# md2pce.net
KiCad netlist of a schematic drawn in EAGLE
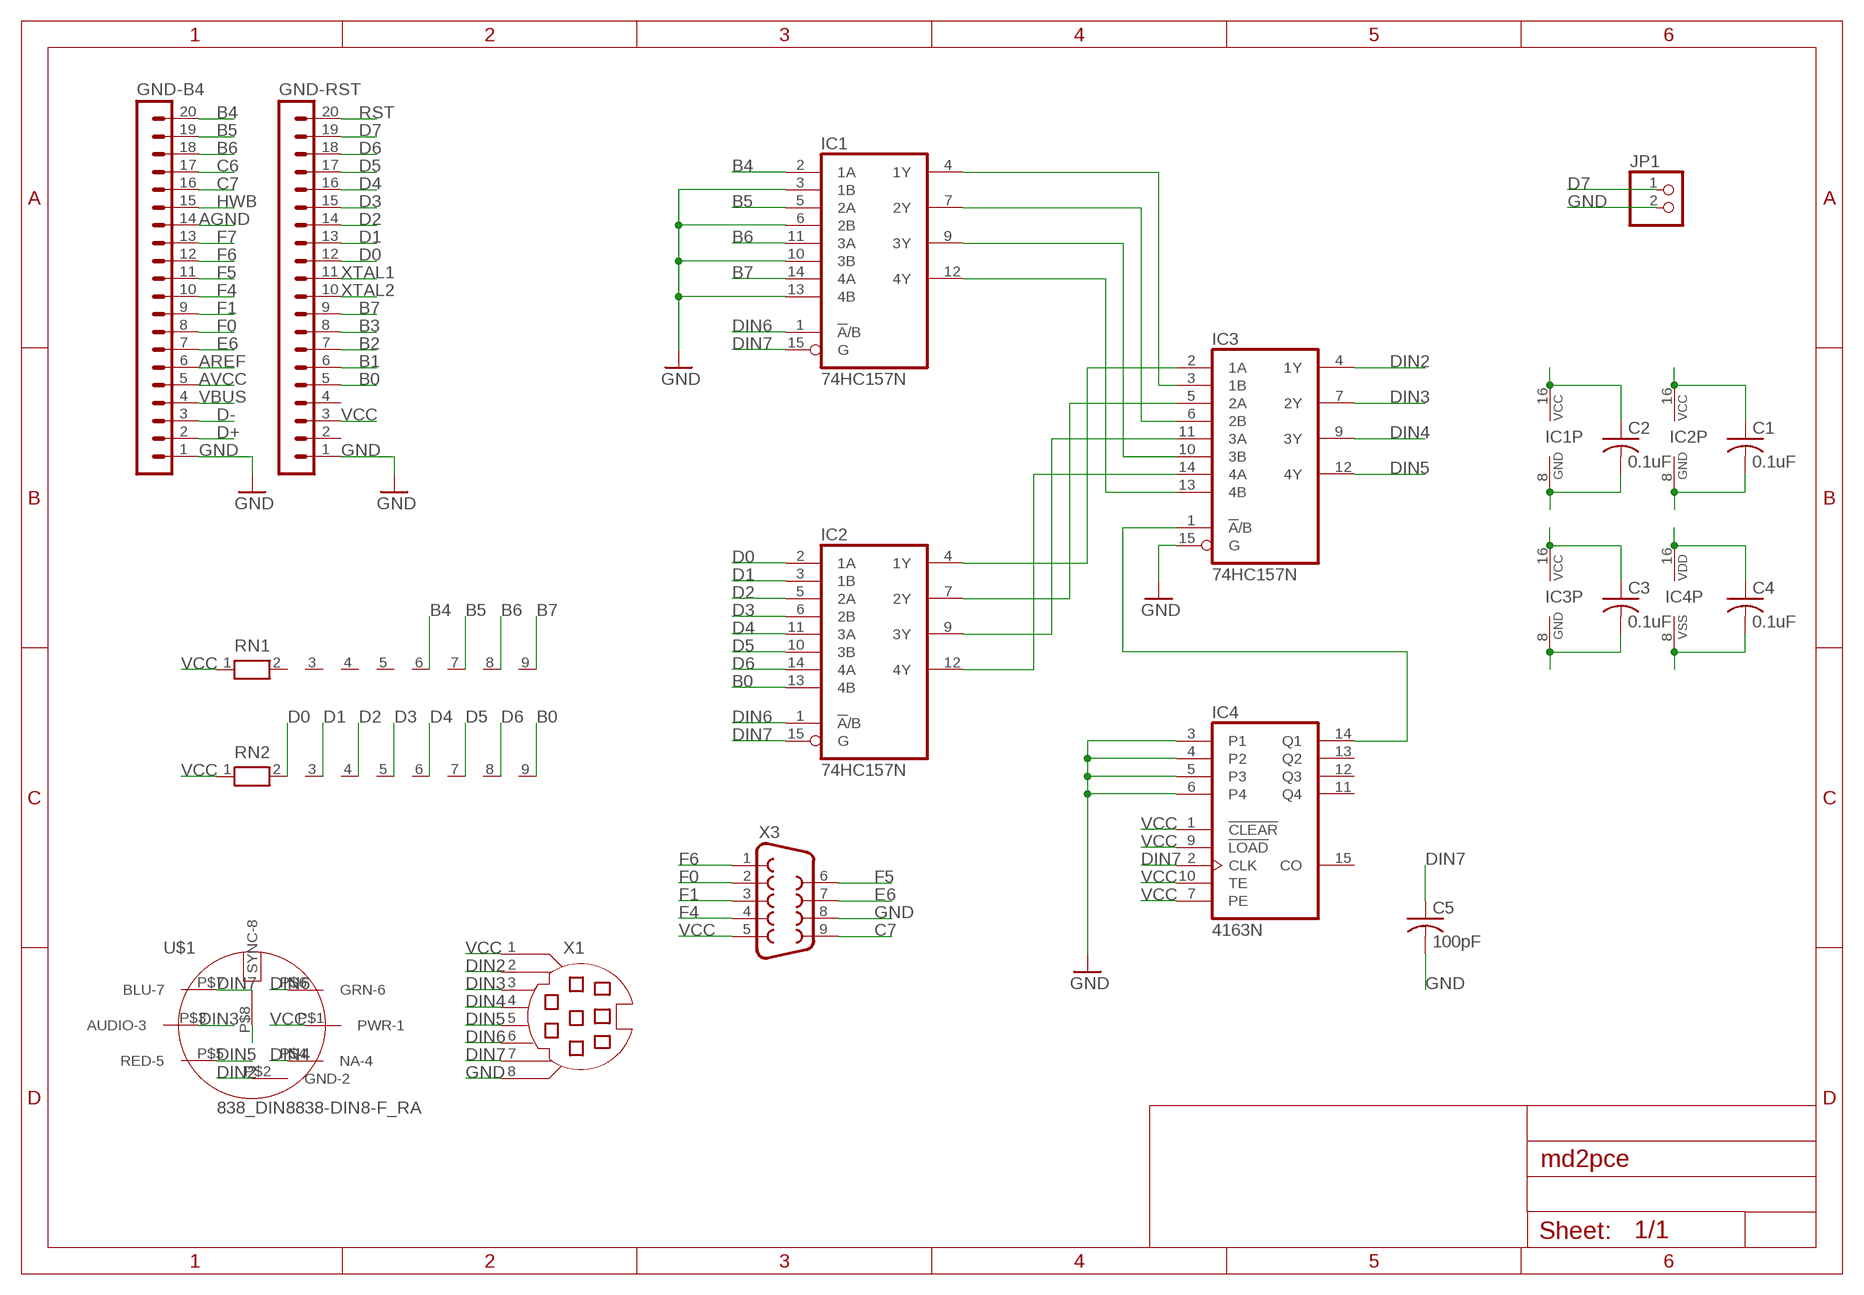
[diagram p0: schematic, sheet 1]

(export (version "E")
  (design (tool "Eeschema 10.0.6"))
  (components
    (comp (ref "C1")
      (value "0.1uF")
      (footprint "eagle-import:C025-024X044")
      (libsource (lib "eagle-import") (part "C-US025-024X044"))
    )
    (comp (ref "C2")
      (value "0.1uF")
      (footprint "eagle-import:C025-024X044")
      (libsource (lib "eagle-import") (part "C-US025-024X044"))
    )
    (comp (ref "C3")
      (value "0.1uF")
      (footprint "eagle-import:C025-024X044")
      (libsource (lib "eagle-import") (part "C-US025-024X044"))
    )
    (comp (ref "C4")
      (value "0.1uF")
      (footprint "eagle-import:C025-024X044")
      (libsource (lib "eagle-import") (part "C-US025-024X044"))
    )
    (comp (ref "C5")
      (value "100pF")
      (footprint "eagle-import:C025-024X044")
      (libsource (lib "eagle-import") (part "C-US025-024X044"))
    )
    (comp (ref "GND-B4")
      (value "MA20-1")
      (footprint "eagle-import:MA20-1")
      (libsource (lib "eagle-import") (part "MA20-1"))
    )
    (comp (ref "GND-RST")
      (value "MA20-1")
      (footprint "eagle-import:MA20-1")
      (libsource (lib "eagle-import") (part "MA20-1"))
    )
    (comp (ref "IC1")
      (value "74HC157N")
      (footprint "eagle-import:DIL16")
      (libsource (lib "eagle-import") (part "74157NHC"))
    )
    (comp (ref "IC2")
      (value "74HC157N")
      (footprint "eagle-import:DIL16")
      (libsource (lib "eagle-import") (part "74157NHC"))
    )
    (comp (ref "IC3")
      (value "74HC157N")
      (footprint "eagle-import:DIL16")
      (libsource (lib "eagle-import") (part "74157NHC"))
    )
    (comp (ref "IC4")
      (value "4163N")
      (footprint "eagle-import:DIL16")
      (libsource (lib "eagle-import") (part "4163N"))
    )
    (comp (ref "JP1")
      (value "PINHD-1X2")
      (footprint "eagle-import:1X02")
      (libsource (lib "eagle-import") (part "PINHD-1X2"))
    )
    (comp (ref "RN1")
      (value "RN08")
      (footprint "eagle-import:RN-9")
      (libsource (lib "eagle-import") (part "RN08"))
    )
    (comp (ref "RN2")
      (value "RN08")
      (footprint "eagle-import:RN-9")
      (libsource (lib "eagle-import") (part "RN08"))
    )
    (comp (ref "U$1")
      (value "838_DIN8838-DIN8-F_RA")
      (footprint "eagle-import:838_DIN8")
      (libsource (lib "eagle-import") (part "838_DIN8838-DIN8-F_RA"))
    )
    (comp (ref "X1")
      (value "MD08SS")
      (footprint "eagle-import:MDIN08SS")
      (libsource (lib "eagle-import") (part "MD08SS"))
    )
    (comp (ref "X3")
      (value "DB9MALE")
      (footprint "eagle-import:DB9_MALE")
      (libsource (lib "eagle-import") (part "DB9MALE"))
    )
  )
  (nets
    (net (code "1") (name "/AGND") (class "Default")
      (node (ref "GND-B4") (pin "14") (pinfunction "14_14") (pintype "passive"))
    )
    (net (code "2") (name "/AREF") (class "Default")
      (node (ref "GND-B4") (pin "6") (pinfunction "6_6") (pintype "passive"))
    )
    (net (code "3") (name "/AVCC") (class "Default")
      (node (ref "GND-B4") (pin "5") (pinfunction "5_5") (pintype "passive"))
    )
    (net (code "4") (name "/B0") (class "Default")
      (node (ref "GND-RST") (pin "5") (pinfunction "5_5") (pintype "passive"))
      (node (ref "IC2") (pin "13") (pinfunction "4B_13") (pintype "input"))
      (node (ref "RN2") (pin "9") (pinfunction "9_9") (pintype "passive"))
    )
    (net (code "5") (name "/B1") (class "Default")
      (node (ref "GND-RST") (pin "6") (pinfunction "6_6") (pintype "passive"))
    )
    (net (code "6") (name "/B2") (class "Default")
      (node (ref "GND-RST") (pin "7") (pinfunction "7_7") (pintype "passive"))
    )
    (net (code "7") (name "/B3") (class "Default")
      (node (ref "GND-RST") (pin "8") (pinfunction "8_8") (pintype "passive"))
    )
    (net (code "8") (name "/B4") (class "Default")
      (node (ref "GND-B4") (pin "20") (pinfunction "20_20") (pintype "passive"))
      (node (ref "IC1") (pin "2") (pinfunction "1A_2") (pintype "input"))
      (node (ref "RN1") (pin "6") (pinfunction "6_6") (pintype "passive"))
    )
    (net (code "9") (name "/B5") (class "Default")
      (node (ref "GND-B4") (pin "19") (pinfunction "19_19") (pintype "passive"))
      (node (ref "IC1") (pin "5") (pinfunction "2A_5") (pintype "input"))
      (node (ref "RN1") (pin "7") (pinfunction "7_7") (pintype "passive"))
    )
    (net (code "10") (name "/B6") (class "Default")
      (node (ref "GND-B4") (pin "18") (pinfunction "18_18") (pintype "passive"))
      (node (ref "IC1") (pin "11") (pinfunction "3A_11") (pintype "input"))
      (node (ref "RN1") (pin "8") (pinfunction "8_8") (pintype "passive"))
    )
    (net (code "11") (name "/B7") (class "Default")
      (node (ref "GND-RST") (pin "9") (pinfunction "9_9") (pintype "passive"))
      (node (ref "IC1") (pin "14") (pinfunction "4A_14") (pintype "input"))
      (node (ref "RN1") (pin "9") (pinfunction "9_9") (pintype "passive"))
    )
    (net (code "12") (name "/C6") (class "Default")
      (node (ref "GND-B4") (pin "17") (pinfunction "17_17") (pintype "passive"))
    )
    (net (code "13") (name "/C7") (class "Default")
      (node (ref "GND-B4") (pin "16") (pinfunction "16_16") (pintype "passive"))
      (node (ref "X3") (pin "9") (pinfunction "9_9") (pintype "passive"))
    )
    (net (code "14") (name "/D+") (class "Default")
      (node (ref "GND-B4") (pin "2") (pinfunction "2_2") (pintype "passive"))
    )
    (net (code "15") (name "/D-") (class "Default")
      (node (ref "GND-B4") (pin "3") (pinfunction "3_3") (pintype "passive"))
    )
    (net (code "16") (name "/D0") (class "Default")
      (node (ref "GND-RST") (pin "12") (pinfunction "12_12") (pintype "passive"))
      (node (ref "IC2") (pin "2") (pinfunction "1A_2") (pintype "input"))
      (node (ref "RN2") (pin "2") (pinfunction "2_2") (pintype "passive"))
    )
    (net (code "17") (name "/D1") (class "Default")
      (node (ref "GND-RST") (pin "13") (pinfunction "13_13") (pintype "passive"))
      (node (ref "IC2") (pin "3") (pinfunction "1B_3") (pintype "input"))
      (node (ref "RN2") (pin "3") (pinfunction "3_3") (pintype "passive"))
    )
    (net (code "18") (name "/D2") (class "Default")
      (node (ref "GND-RST") (pin "14") (pinfunction "14_14") (pintype "passive"))
      (node (ref "IC2") (pin "5") (pinfunction "2A_5") (pintype "input"))
      (node (ref "RN2") (pin "4") (pinfunction "4_4") (pintype "passive"))
    )
    (net (code "19") (name "/D3") (class "Default")
      (node (ref "GND-RST") (pin "15") (pinfunction "15_15") (pintype "passive"))
      (node (ref "IC2") (pin "6") (pinfunction "2B_6") (pintype "input"))
      (node (ref "RN2") (pin "5") (pinfunction "5_5") (pintype "passive"))
    )
    (net (code "20") (name "/D4") (class "Default")
      (node (ref "GND-RST") (pin "16") (pinfunction "16_16") (pintype "passive"))
      (node (ref "IC2") (pin "11") (pinfunction "3A_11") (pintype "input"))
      (node (ref "RN2") (pin "6") (pinfunction "6_6") (pintype "passive"))
    )
    (net (code "21") (name "/D5") (class "Default")
      (node (ref "GND-RST") (pin "17") (pinfunction "17_17") (pintype "passive"))
      (node (ref "IC2") (pin "10") (pinfunction "3B_10") (pintype "input"))
      (node (ref "RN2") (pin "7") (pinfunction "7_7") (pintype "passive"))
    )
    (net (code "22") (name "/D6") (class "Default")
      (node (ref "GND-RST") (pin "18") (pinfunction "18_18") (pintype "passive"))
      (node (ref "IC2") (pin "14") (pinfunction "4A_14") (pintype "input"))
      (node (ref "RN2") (pin "8") (pinfunction "8_8") (pintype "passive"))
    )
    (net (code "23") (name "/D7") (class "Default")
      (node (ref "GND-RST") (pin "19") (pinfunction "19_19") (pintype "passive"))
      (node (ref "JP1") (pin "1") (pinfunction "1_1") (pintype "passive"))
    )
    (net (code "24") (name "/DIN2") (class "Default")
      (node (ref "IC3") (pin "4") (pinfunction "1Y_4") (pintype "output"))
      (node (ref "U$1") (pin "P$2") (pinfunction "GND-2_P$2") (pintype "bidirectional"))
      (node (ref "X1") (pin "2") (pinfunction "2_2") (pintype "passive"))
    )
    (net (code "25") (name "/DIN3") (class "Default")
      (node (ref "IC3") (pin "7") (pinfunction "2Y_7") (pintype "output"))
      (node (ref "U$1") (pin "P$3") (pinfunction "AUDIO-3_P$3") (pintype "bidirectional"))
      (node (ref "X1") (pin "3") (pinfunction "3_3") (pintype "passive"))
    )
    (net (code "26") (name "/DIN4") (class "Default")
      (node (ref "IC3") (pin "9") (pinfunction "3Y_9") (pintype "output"))
      (node (ref "U$1") (pin "P$4") (pinfunction "NA-4_P$4") (pintype "bidirectional"))
      (node (ref "X1") (pin "4") (pinfunction "4_4") (pintype "passive"))
    )
    (net (code "27") (name "/DIN5") (class "Default")
      (node (ref "IC3") (pin "12") (pinfunction "4Y_12") (pintype "output"))
      (node (ref "U$1") (pin "P$5") (pinfunction "RED-5_P$5") (pintype "bidirectional"))
      (node (ref "X1") (pin "5") (pinfunction "5_5") (pintype "passive"))
    )
    (net (code "28") (name "/DIN6") (class "Default")
      (node (ref "IC1") (pin "1") (pinfunction "~{A}/B_1") (pintype "input"))
      (node (ref "IC2") (pin "1") (pinfunction "~{A}/B_1") (pintype "input"))
      (node (ref "U$1") (pin "P$6") (pinfunction "GRN-6_P$6") (pintype "bidirectional"))
      (node (ref "X1") (pin "6") (pinfunction "6_6") (pintype "passive"))
    )
    (net (code "29") (name "/DIN7") (class "Default")
      (node (ref "C5") (pin "1") (pinfunction "1_1") (pintype "passive"))
      (node (ref "IC1") (pin "15") (pinfunction "G_15") (pintype "input"))
      (node (ref "IC2") (pin "15") (pinfunction "G_15") (pintype "input"))
      (node (ref "IC4") (pin "2") (pinfunction "CLK_2") (pintype "input"))
      (node (ref "U$1") (pin "P$7") (pinfunction "BLU-7_P$7") (pintype "bidirectional"))
      (node (ref "X1") (pin "7") (pinfunction "7_7") (pintype "passive"))
    )
    (net (code "30") (name "/E6") (class "Default")
      (node (ref "GND-B4") (pin "7") (pinfunction "7_7") (pintype "passive"))
      (node (ref "X3") (pin "7") (pinfunction "7_7") (pintype "passive"))
    )
    (net (code "31") (name "/F0") (class "Default")
      (node (ref "GND-B4") (pin "8") (pinfunction "8_8") (pintype "passive"))
      (node (ref "X3") (pin "2") (pinfunction "2_2") (pintype "passive"))
    )
    (net (code "32") (name "/F1") (class "Default")
      (node (ref "GND-B4") (pin "9") (pinfunction "9_9") (pintype "passive"))
      (node (ref "X3") (pin "3") (pinfunction "3_3") (pintype "passive"))
    )
    (net (code "33") (name "/F4") (class "Default")
      (node (ref "GND-B4") (pin "10") (pinfunction "10_10") (pintype "passive"))
      (node (ref "X3") (pin "4") (pinfunction "4_4") (pintype "passive"))
    )
    (net (code "34") (name "/F5") (class "Default")
      (node (ref "GND-B4") (pin "11") (pinfunction "11_11") (pintype "passive"))
      (node (ref "X3") (pin "6") (pinfunction "6_6") (pintype "passive"))
    )
    (net (code "35") (name "/F6") (class "Default")
      (node (ref "GND-B4") (pin "12") (pinfunction "12_12") (pintype "passive"))
      (node (ref "X3") (pin "1") (pinfunction "1_1") (pintype "passive"))
    )
    (net (code "36") (name "/F7") (class "Default")
      (node (ref "GND-B4") (pin "13") (pinfunction "13_13") (pintype "passive"))
    )
    (net (code "37") (name "/HWB") (class "Default")
      (node (ref "GND-B4") (pin "15") (pinfunction "15_15") (pintype "passive"))
    )
    (net (code "38") (name "/RST") (class "Default")
      (node (ref "GND-RST") (pin "20") (pinfunction "20_20") (pintype "passive"))
    )
    (net (code "39") (name "/VBUS") (class "Default")
      (node (ref "GND-B4") (pin "4") (pinfunction "4_4") (pintype "passive"))
    )
    (net (code "40") (name "/VCC") (class "Default")
      (node (ref "C1") (pin "1") (pinfunction "1_1") (pintype "passive"))
      (node (ref "C2") (pin "1") (pinfunction "1_1") (pintype "passive"))
      (node (ref "C3") (pin "1") (pinfunction "1_1") (pintype "passive"))
      (node (ref "C4") (pin "1") (pinfunction "1_1") (pintype "passive"))
      (node (ref "GND-RST") (pin "3") (pinfunction "3_3") (pintype "passive"))
      (node (ref "IC1") (pin "16") (pinfunction "VCC_16") (pintype "power_in"))
      (node (ref "IC2") (pin "16") (pinfunction "VCC_16") (pintype "power_in"))
      (node (ref "IC3") (pin "16") (pinfunction "VCC_16") (pintype "power_in"))
      (node (ref "IC4") (pin "1") (pinfunction "~{CLEAR}_1") (pintype "input"))
      (node (ref "IC4") (pin "10") (pinfunction "TE_10") (pintype "input"))
      (node (ref "IC4") (pin "16") (pinfunction "VDD_16") (pintype "power_in"))
      (node (ref "IC4") (pin "7") (pinfunction "PE_7") (pintype "input"))
      (node (ref "IC4") (pin "9") (pinfunction "~{LOAD}_9") (pintype "input"))
      (node (ref "RN1") (pin "1") (pinfunction "1_1") (pintype "passive"))
      (node (ref "RN2") (pin "1") (pinfunction "1_1") (pintype "passive"))
      (node (ref "U$1") (pin "P$1") (pinfunction "PWR-1_P$1") (pintype "power_in"))
      (node (ref "X1") (pin "1") (pinfunction "1_1") (pintype "passive"))
      (node (ref "X3") (pin "5") (pinfunction "5_5") (pintype "passive"))
    )
    (net (code "41") (name "/XTAL1") (class "Default")
      (node (ref "GND-RST") (pin "11") (pinfunction "11_11") (pintype "passive"))
    )
    (net (code "42") (name "/XTAL2") (class "Default")
      (node (ref "GND-RST") (pin "10") (pinfunction "10_10") (pintype "passive"))
    )
    (net (code "43") (name "GND") (class "Default")
      (node (ref "C1") (pin "2") (pinfunction "2_2") (pintype "passive"))
      (node (ref "C2") (pin "2") (pinfunction "2_2") (pintype "passive"))
      (node (ref "C3") (pin "2") (pinfunction "2_2") (pintype "passive"))
      (node (ref "C4") (pin "2") (pinfunction "2_2") (pintype "passive"))
      (node (ref "C5") (pin "2") (pinfunction "2_2") (pintype "passive"))
      (node (ref "GND-B4") (pin "1") (pinfunction "1_1") (pintype "passive"))
      (node (ref "GND-RST") (pin "1") (pinfunction "1_1") (pintype "passive"))
      (node (ref "IC1") (pin "10") (pinfunction "3B_10") (pintype "input"))
      (node (ref "IC1") (pin "13") (pinfunction "4B_13") (pintype "input"))
      (node (ref "IC1") (pin "3") (pinfunction "1B_3") (pintype "input"))
      (node (ref "IC1") (pin "6") (pinfunction "2B_6") (pintype "input"))
      (node (ref "IC1") (pin "8") (pinfunction "GND_8") (pintype "power_in"))
      (node (ref "IC2") (pin "8") (pinfunction "GND_8") (pintype "power_in"))
      (node (ref "IC3") (pin "15") (pinfunction "G_15") (pintype "input"))
      (node (ref "IC3") (pin "8") (pinfunction "GND_8") (pintype "power_in"))
      (node (ref "IC4") (pin "3") (pinfunction "P1_3") (pintype "input"))
      (node (ref "IC4") (pin "4") (pinfunction "P2_4") (pintype "input"))
      (node (ref "IC4") (pin "5") (pinfunction "P3_5") (pintype "input"))
      (node (ref "IC4") (pin "6") (pinfunction "P4_6") (pintype "input"))
      (node (ref "IC4") (pin "8") (pinfunction "VSS_8") (pintype "power_in"))
      (node (ref "JP1") (pin "2") (pinfunction "2_2") (pintype "passive"))
      (node (ref "U$1") (pin "P$8") (pinfunction "SYNC-8_P$8") (pintype "bidirectional"))
      (node (ref "X1") (pin "8") (pinfunction "8_8") (pintype "passive"))
      (node (ref "X3") (pin "8") (pinfunction "8_8") (pintype "passive"))
    )
    (net (code "44") (name "Net-(IC1A-1Y)") (class "Default")
      (node (ref "IC1") (pin "4") (pinfunction "1Y_4") (pintype "output"))
      (node (ref "IC3") (pin "3") (pinfunction "1B_3") (pintype "input"))
    )
    (net (code "45") (name "Net-(IC1A-2Y)") (class "Default")
      (node (ref "IC1") (pin "7") (pinfunction "2Y_7") (pintype "output"))
      (node (ref "IC3") (pin "6") (pinfunction "2B_6") (pintype "input"))
    )
    (net (code "46") (name "Net-(IC1A-3Y)") (class "Default")
      (node (ref "IC1") (pin "9") (pinfunction "3Y_9") (pintype "output"))
      (node (ref "IC3") (pin "10") (pinfunction "3B_10") (pintype "input"))
    )
    (net (code "47") (name "Net-(IC1A-4Y)") (class "Default")
      (node (ref "IC1") (pin "12") (pinfunction "4Y_12") (pintype "output"))
      (node (ref "IC3") (pin "13") (pinfunction "4B_13") (pintype "input"))
    )
    (net (code "48") (name "Net-(IC2A-1Y)") (class "Default")
      (node (ref "IC2") (pin "4") (pinfunction "1Y_4") (pintype "output"))
      (node (ref "IC3") (pin "2") (pinfunction "1A_2") (pintype "input"))
    )
    (net (code "49") (name "Net-(IC2A-2Y)") (class "Default")
      (node (ref "IC2") (pin "7") (pinfunction "2Y_7") (pintype "output"))
      (node (ref "IC3") (pin "5") (pinfunction "2A_5") (pintype "input"))
    )
    (net (code "50") (name "Net-(IC2A-3Y)") (class "Default")
      (node (ref "IC2") (pin "9") (pinfunction "3Y_9") (pintype "output"))
      (node (ref "IC3") (pin "11") (pinfunction "3A_11") (pintype "input"))
    )
    (net (code "51") (name "Net-(IC2A-4Y)") (class "Default")
      (node (ref "IC2") (pin "12") (pinfunction "4Y_12") (pintype "output"))
      (node (ref "IC3") (pin "14") (pinfunction "4A_14") (pintype "input"))
    )
    (net (code "52") (name "Net-(IC3A-~{A}{slash}B)") (class "Default")
      (node (ref "IC3") (pin "1") (pinfunction "~{A}/B_1") (pintype "input"))
      (node (ref "IC4") (pin "14") (pinfunction "Q1_14") (pintype "output"))
    )
    (net (code "53") (name "unconnected-(GND-RST-Pad2)") (class "Default")
      (node (ref "GND-RST") (pin "2") (pinfunction "2_2") (pintype "passive"))
    )
    (net (code "54") (name "unconnected-(GND-RST-Pad4)") (class "Default")
      (node (ref "GND-RST") (pin "4") (pinfunction "4_4") (pintype "passive"))
    )
    (net (code "55") (name "unconnected-(IC4A-CO-Pad15)") (class "Default")
      (node (ref "IC4") (pin "15") (pinfunction "CO_15") (pintype "output"))
    )
    (net (code "56") (name "unconnected-(IC4A-Q2-Pad13)") (class "Default")
      (node (ref "IC4") (pin "13") (pinfunction "Q2_13") (pintype "output"))
    )
    (net (code "57") (name "unconnected-(IC4A-Q3-Pad12)") (class "Default")
      (node (ref "IC4") (pin "12") (pinfunction "Q3_12") (pintype "output"))
    )
    (net (code "58") (name "unconnected-(IC4A-Q4-Pad11)") (class "Default")
      (node (ref "IC4") (pin "11") (pinfunction "Q4_11") (pintype "output"))
    )
    (net (code "59") (name "unconnected-(RN1-Pad2)") (class "Default")
      (node (ref "RN1") (pin "2") (pinfunction "2_2") (pintype "passive"))
    )
    (net (code "60") (name "unconnected-(RN1-Pad3)") (class "Default")
      (node (ref "RN1") (pin "3") (pinfunction "3_3") (pintype "passive"))
    )
    (net (code "61") (name "unconnected-(RN1-Pad4)") (class "Default")
      (node (ref "RN1") (pin "4") (pinfunction "4_4") (pintype "passive"))
    )
    (net (code "62") (name "unconnected-(RN1-Pad5)") (class "Default")
      (node (ref "RN1") (pin "5") (pinfunction "5_5") (pintype "passive"))
    )
  )
)
